# openservo-v28.net
KiCad netlist of a schematic drawn in EAGLE
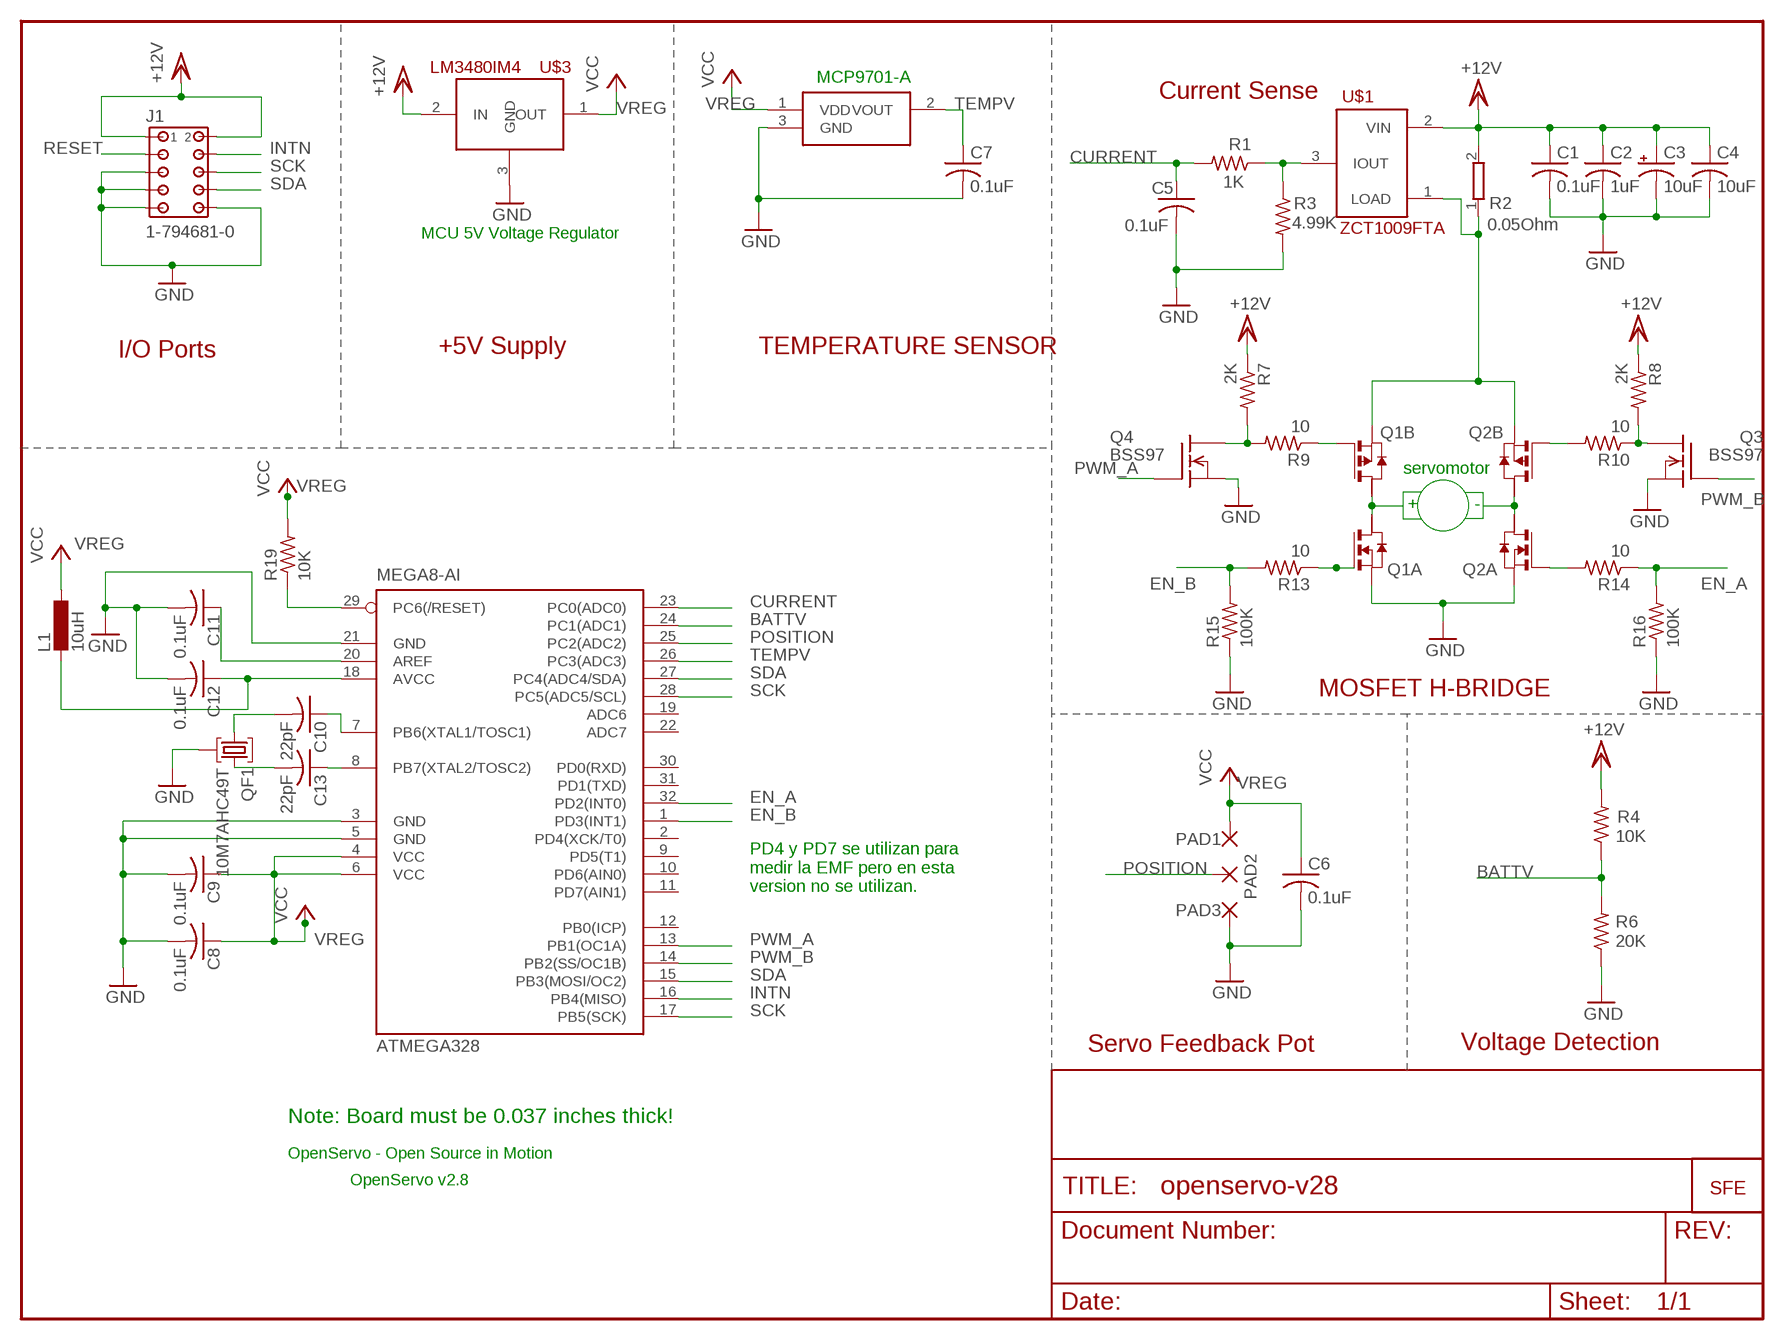
[diagram p0: schematic, sheet 1]

(export (version "E")
  (design (tool "Eeschema 10.0.6"))
  (components
    (comp (ref "ATMEGA328")
      (value "MEGA8-AI")
      (footprint "eagle-import:TQFP32-08")
      (fields (field (name "MPN") "ATMEGA8-16AU"))
      (libsource (lib "eagle-import") (part "MEGA8-AI"))
    )
    (comp (ref "C1")
      (value "0.1uF")
      (footprint "eagle-import:C0402")
      (libsource (lib "eagle-import") (part "C-USC0402"))
    )
    (comp (ref "C2")
      (value "1uF")
      (footprint "eagle-import:C0402")
      (libsource (lib "eagle-import") (part "C-USC0402"))
    )
    (comp (ref "C3")
      (value "10uF")
      (footprint "eagle-import:EIA3528")
      (libsource (lib "eagle-import") (part "CAP_POL3528"))
    )
    (comp (ref "C4")
      (value "10uF")
      (footprint "eagle-import:C0402")
      (libsource (lib "eagle-import") (part "C-USC0402"))
    )
    (comp (ref "C5")
      (value "0.1uF")
      (footprint "eagle-import:C0402")
      (libsource (lib "eagle-import") (part "C-USC0402"))
    )
    (comp (ref "C6")
      (value "0.1uF")
      (footprint "eagle-import:C0402")
      (libsource (lib "eagle-import") (part "C-USC0402"))
    )
    (comp (ref "C7")
      (value "0.1uF")
      (footprint "eagle-import:C0402")
      (libsource (lib "eagle-import") (part "C-USC0402"))
    )
    (comp (ref "C8")
      (value "0.1uF")
      (footprint "eagle-import:C0402")
      (libsource (lib "eagle-import") (part "C-USC0402"))
    )
    (comp (ref "C9")
      (value "0.1uF")
      (footprint "eagle-import:C0402")
      (libsource (lib "eagle-import") (part "C-USC0402"))
    )
    (comp (ref "C10")
      (value "22pF")
      (footprint "eagle-import:C0402")
      (libsource (lib "eagle-import") (part "C-USC0402"))
    )
    (comp (ref "C11")
      (value "0.1uF")
      (footprint "eagle-import:C0402")
      (libsource (lib "eagle-import") (part "C-USC0402"))
    )
    (comp (ref "C12")
      (value "0.1uF")
      (footprint "eagle-import:C0402")
      (libsource (lib "eagle-import") (part "C-USC0402"))
    )
    (comp (ref "C13")
      (value "22pF")
      (footprint "eagle-import:C0402")
      (libsource (lib "eagle-import") (part "C-USC0402"))
    )
    (comp (ref "J1")
      (value "1-794681-0")
      (footprint "eagle-import:1-794681-0")
      (libsource (lib "eagle-import") (part "1-794681-0"))
    )
    (comp (ref "L1")
      (value "10uH")
      (footprint "eagle-import:0204_5")
      (libsource (lib "eagle-import") (part "L-EU0204/5"))
    )
    (comp (ref "PAD1")
      (value "1,6/0,9")
      (footprint "eagle-import:1,6_0,9")
      (libsource (lib "eagle-import") (part "1,6/0,9"))
    )
    (comp (ref "PAD2")
      (value "1,6/0,9")
      (footprint "eagle-import:1,6_0,9")
      (libsource (lib "eagle-import") (part "1,6/0,9"))
    )
    (comp (ref "PAD3")
      (value "1,6/0,9")
      (footprint "eagle-import:1,6_0,9")
      (libsource (lib "eagle-import") (part "1,6/0,9"))
    )
    (comp (ref "Q1")
      (value "PN_MOSFET-SO8")
      (footprint "eagle-import:SO8")
      (libsource (lib "eagle-import") (part "PN_MOSFET-SO8"))
    )
    (comp (ref "Q2")
      (value "PN_MOSFET-SO8")
      (footprint "eagle-import:SO8")
      (libsource (lib "eagle-import") (part "PN_MOSFET-SO8"))
    )
    (comp (ref "Q3")
      (value "BSS97")
      (footprint "eagle-import:TO202")
      (libsource (lib "eagle-import") (part "BSS97"))
    )
    (comp (ref "Q4")
      (value "BSS97")
      (footprint "eagle-import:TO202")
      (libsource (lib "eagle-import") (part "BSS97"))
    )
    (comp (ref "QF1")
      (value "10M7AHC49T")
      (footprint "eagle-import:HC49U")
      (libsource (lib "eagle-import") (part "10MAHC49T7"))
    )
    (comp (ref "R1")
      (value "1K")
      (footprint "eagle-import:R0402")
      (libsource (lib "eagle-import") (part "R-US_R0402"))
    )
    (comp (ref "R2")
      (value "0.05Ohm")
      (footprint "eagle-import:R1206W")
      (libsource (lib "eagle-import") (part "R1206W"))
    )
    (comp (ref "R3")
      (value "4.99K")
      (footprint "eagle-import:R0402")
      (libsource (lib "eagle-import") (part "R-US_R0402"))
    )
    (comp (ref "R4")
      (value "10K")
      (footprint "eagle-import:R0402")
      (libsource (lib "eagle-import") (part "R-US_R0402"))
    )
    (comp (ref "R6")
      (value "20K")
      (footprint "eagle-import:R0402")
      (libsource (lib "eagle-import") (part "R-US_R0402"))
    )
    (comp (ref "R7")
      (value "2K")
      (footprint "eagle-import:R0402")
      (libsource (lib "eagle-import") (part "R-US_R0402"))
    )
    (comp (ref "R8")
      (value "2K")
      (footprint "eagle-import:R0402")
      (libsource (lib "eagle-import") (part "R-US_R0402"))
    )
    (comp (ref "R9")
      (value "10")
      (footprint "eagle-import:R0402")
      (libsource (lib "eagle-import") (part "R-US_R0402"))
    )
    (comp (ref "R10")
      (value "10")
      (footprint "eagle-import:R0402")
      (libsource (lib "eagle-import") (part "R-US_R0402"))
    )
    (comp (ref "R13")
      (value "10")
      (footprint "eagle-import:R0402")
      (libsource (lib "eagle-import") (part "R-US_R0402"))
    )
    (comp (ref "R14")
      (value "10")
      (footprint "eagle-import:R0402")
      (libsource (lib "eagle-import") (part "R-US_R0402"))
    )
    (comp (ref "R15")
      (value "100K")
      (footprint "eagle-import:R0402")
      (libsource (lib "eagle-import") (part "R-US_R0402"))
    )
    (comp (ref "R16")
      (value "100K")
      (footprint "eagle-import:R0402")
      (libsource (lib "eagle-import") (part "R-US_R0402"))
    )
    (comp (ref "R19")
      (value "10K")
      (footprint "eagle-import:R0402")
      (libsource (lib "eagle-import") (part "R-US_R0402"))
    )
    (comp (ref "U$1")
      (value "ZCT1009FTA")
      (footprint "eagle-import:SOT23-3")
      (libsource (lib "eagle-import") (part "ZCT1009FTA"))
    )
    (comp (ref "U$2")
      (value "MCP9701-A")
      (footprint "eagle-import:TO-92")
      (libsource (lib "eagle-import") (part "MCP9701-A"))
    )
    (comp (ref "U$3")
      (value "LM3480IM4")
      (footprint "eagle-import:SOT23-3")
      (libsource (lib "eagle-import") (part "LM3480IM4"))
    )
    (comp (ref "U$7")
      (value "LOGO-SFESK")
      (footprint "eagle-import:SFE-LOGO-FLAME")
      (libsource (lib "eagle-import") (part "LOGO-SFESK"))
    )
  )
  (nets
    (net (code "1") (name "+12V") (class "Default")
      (node (ref "C1") (pin "1") (pinfunction "1_1") (pintype "passive"))
      (node (ref "C2") (pin "1") (pinfunction "1_1") (pintype "passive"))
      (node (ref "C3") (pin "A") (pinfunction "+_A") (pintype "passive"))
      (node (ref "C4") (pin "1") (pinfunction "1_1") (pintype "passive"))
      (node (ref "J1") (pin "1") (pinfunction "1_1") (pintype "passive"))
      (node (ref "J1") (pin "2") (pinfunction "2_2") (pintype "passive"))
      (node (ref "R2") (pin "2") (pinfunction "2_2") (pintype "passive"))
      (node (ref "R4") (pin "2") (pinfunction "2_2") (pintype "passive"))
      (node (ref "R7") (pin "1") (pinfunction "1_1") (pintype "passive"))
      (node (ref "R8") (pin "1") (pinfunction "1_1") (pintype "passive"))
      (node (ref "U$1") (pin "2") (pinfunction "VIN_2") (pintype "bidirectional"))
      (node (ref "U$3") (pin "2") (pinfunction "IN_2") (pintype "bidirectional"))
    )
    (net (code "2") (name "/BATTV") (class "Default")
      (node (ref "ATMEGA328") (pin "24") (pinfunction "PC1(ADC1)_24") (pintype "bidirectional"))
      (node (ref "R4") (pin "1") (pinfunction "1_1") (pintype "passive"))
      (node (ref "R6") (pin "2") (pinfunction "2_2") (pintype "passive"))
    )
    (net (code "3") (name "/CURRENT") (class "Default")
      (node (ref "ATMEGA328") (pin "23") (pinfunction "PC0(ADC0)_23") (pintype "bidirectional"))
      (node (ref "C5") (pin "1") (pinfunction "1_1") (pintype "passive"))
      (node (ref "R1") (pin "2") (pinfunction "2_2") (pintype "passive"))
    )
    (net (code "4") (name "/EN_A") (class "Default")
      (node (ref "ATMEGA328") (pin "32") (pinfunction "PD2(INT0)_32") (pintype "bidirectional"))
      (node (ref "R14") (pin "1") (pinfunction "1_1") (pintype "passive"))
      (node (ref "R16") (pin "2") (pinfunction "2_2") (pintype "passive"))
    )
    (net (code "5") (name "/EN_B") (class "Default")
      (node (ref "ATMEGA328") (pin "1") (pinfunction "PD3(INT1)_1") (pintype "bidirectional"))
      (node (ref "R13") (pin "2") (pinfunction "2_2") (pintype "passive"))
      (node (ref "R15") (pin "2") (pinfunction "2_2") (pintype "passive"))
    )
    (net (code "6") (name "/INTN") (class "Default")
      (node (ref "ATMEGA328") (pin "16") (pinfunction "PB4(MISO)_16") (pintype "bidirectional"))
      (node (ref "J1") (pin "4") (pinfunction "4_4") (pintype "passive"))
    )
    (net (code "7") (name "/POSITION") (class "Default")
      (node (ref "ATMEGA328") (pin "25") (pinfunction "PC2(ADC2)_25") (pintype "bidirectional"))
      (node (ref "PAD2") (pin "1") (pinfunction "P_1") (pintype "passive"))
    )
    (net (code "8") (name "/PWM_A") (class "Default")
      (node (ref "ATMEGA328") (pin "13") (pinfunction "PB1(OC1A)_13") (pintype "bidirectional"))
      (node (ref "Q4") (pin "3") (pinfunction "G_3") (pintype "passive"))
    )
    (net (code "9") (name "/PWM_B") (class "Default")
      (node (ref "ATMEGA328") (pin "14") (pinfunction "PB2(SS/OC1B)_14") (pintype "bidirectional"))
      (node (ref "Q3") (pin "3") (pinfunction "G_3") (pintype "passive"))
    )
    (net (code "10") (name "/RESET") (class "Default")
      (node (ref "ATMEGA328") (pin "29") (pinfunction "PC6(/RESET)_29") (pintype "bidirectional"))
      (node (ref "J1") (pin "3") (pinfunction "3_3") (pintype "passive"))
      (node (ref "R19") (pin "1") (pinfunction "1_1") (pintype "passive"))
    )
    (net (code "11") (name "/SCK") (class "Default")
      (node (ref "ATMEGA328") (pin "17") (pinfunction "PB5(SCK)_17") (pintype "bidirectional"))
      (node (ref "ATMEGA328") (pin "28") (pinfunction "PC5(ADC5/SCL)_28") (pintype "bidirectional"))
      (node (ref "J1") (pin "6") (pinfunction "6_6") (pintype "passive"))
    )
    (net (code "12") (name "/SDA") (class "Default")
      (node (ref "ATMEGA328") (pin "15") (pinfunction "PB3(MOSI/OC2)_15") (pintype "bidirectional"))
      (node (ref "ATMEGA328") (pin "27") (pinfunction "PC4(ADC4/SDA)_27") (pintype "bidirectional"))
      (node (ref "J1") (pin "8") (pinfunction "8_8") (pintype "passive"))
    )
    (net (code "13") (name "/TEMPV") (class "Default")
      (node (ref "ATMEGA328") (pin "26") (pinfunction "PC3(ADC3)_26") (pintype "bidirectional"))
      (node (ref "C7") (pin "1") (pinfunction "1_1") (pintype "passive"))
      (node (ref "U$2") (pin "2") (pinfunction "VOUT_2") (pintype "bidirectional"))
    )
    (net (code "14") (name "GND") (class "Default")
      (node (ref "ATMEGA328") (pin "21") (pinfunction "GND_21") (pintype "power_in"))
      (node (ref "ATMEGA328") (pin "3") (pinfunction "GND_3") (pintype "power_in"))
      (node (ref "ATMEGA328") (pin "5") (pinfunction "GND_5") (pintype "power_in"))
      (node (ref "C1") (pin "2") (pinfunction "2_2") (pintype "passive"))
      (node (ref "C11") (pin "2") (pinfunction "2_2") (pintype "passive"))
      (node (ref "C12") (pin "2") (pinfunction "2_2") (pintype "passive"))
      (node (ref "C2") (pin "2") (pinfunction "2_2") (pintype "passive"))
      (node (ref "C3") (pin "C") (pinfunction "-_C") (pintype "passive"))
      (node (ref "C4") (pin "2") (pinfunction "2_2") (pintype "passive"))
      (node (ref "C5") (pin "2") (pinfunction "2_2") (pintype "passive"))
      (node (ref "C6") (pin "2") (pinfunction "2_2") (pintype "passive"))
      (node (ref "C7") (pin "2") (pinfunction "2_2") (pintype "passive"))
      (node (ref "C8") (pin "2") (pinfunction "2_2") (pintype "passive"))
      (node (ref "C9") (pin "2") (pinfunction "2_2") (pintype "passive"))
      (node (ref "J1") (pin "10") (pinfunction "10_10") (pintype "passive"))
      (node (ref "J1") (pin "5") (pinfunction "5_5") (pintype "passive"))
      (node (ref "J1") (pin "7") (pinfunction "7_7") (pintype "passive"))
      (node (ref "J1") (pin "9") (pinfunction "9_9") (pintype "passive"))
      (node (ref "PAD3") (pin "1") (pinfunction "P_1") (pintype "passive"))
      (node (ref "Q1") (pin "1") (pinfunction "S_1") (pintype "passive"))
      (node (ref "Q2") (pin "1") (pinfunction "S_1") (pintype "passive"))
      (node (ref "Q3") (pin "1") (pinfunction "S_1") (pintype "passive"))
      (node (ref "Q4") (pin "1") (pinfunction "S_1") (pintype "passive"))
      (node (ref "QF1") (pin "2") (pinfunction "2_2") (pintype "passive"))
      (node (ref "R15") (pin "1") (pinfunction "1_1") (pintype "passive"))
      (node (ref "R16") (pin "1") (pinfunction "1_1") (pintype "passive"))
      (node (ref "R3") (pin "2") (pinfunction "2_2") (pintype "passive"))
      (node (ref "R6") (pin "1") (pinfunction "1_1") (pintype "passive"))
      (node (ref "U$2") (pin "3") (pinfunction "GND_3") (pintype "bidirectional"))
      (node (ref "U$3") (pin "3") (pinfunction "GND_3") (pintype "bidirectional"))
    )
    (net (code "15") (name "Net-(ATMEGA328-AREF)") (class "Default")
      (node (ref "ATMEGA328") (pin "20") (pinfunction "AREF_20") (pintype "passive"))
      (node (ref "C11") (pin "1") (pinfunction "1_1") (pintype "passive"))
    )
    (net (code "16") (name "Net-(ATMEGA328-AVCC)") (class "Default")
      (node (ref "ATMEGA328") (pin "18") (pinfunction "AVCC_18") (pintype "power_in"))
      (node (ref "C12") (pin "1") (pinfunction "1_1") (pintype "passive"))
      (node (ref "L1") (pin "2") (pinfunction "2_2") (pintype "passive"))
    )
    (net (code "17") (name "Net-(ATMEGA328-PB6(XTAL1{slash}TOSC1))") (class "Default")
      (node (ref "ATMEGA328") (pin "7") (pinfunction "PB6(XTAL1/TOSC1)_7") (pintype "bidirectional"))
      (node (ref "C10") (pin "1") (pinfunction "1_1") (pintype "passive"))
    )
    (net (code "18") (name "Net-(ATMEGA328-PB7(XTAL2{slash}TOSC2))") (class "Default")
      (node (ref "ATMEGA328") (pin "8") (pinfunction "PB7(XTAL2/TOSC2)_8") (pintype "bidirectional"))
      (node (ref "C13") (pin "1") (pinfunction "1_1") (pintype "passive"))
    )
    (net (code "19") (name "Net-(C10-Pad2)") (class "Default")
      (node (ref "C10") (pin "2") (pinfunction "2_2") (pintype "passive"))
      (node (ref "QF1") (pin "1") (pinfunction "1_1") (pintype "passive"))
    )
    (net (code "20") (name "Net-(C13-Pad2)") (class "Default")
      (node (ref "C13") (pin "2") (pinfunction "2_2") (pintype "passive"))
      (node (ref "QF1") (pin "3") (pinfunction "3_3") (pintype "passive"))
    )
    (net (code "21") (name "Net-(Q1A-D)") (class "Default")
      (node (ref "Q1") (pin "5") (pinfunction "D_5") (pintype "passive"))
      (node (ref "Q1") (pin "7") (pinfunction "D_7") (pintype "passive"))
    )
    (net (code "22") (name "Net-(Q1A-G)") (class "Default")
      (node (ref "Q1") (pin "2") (pinfunction "G_2") (pintype "passive"))
      (node (ref "R13") (pin "1") (pinfunction "1_1") (pintype "passive"))
    )
    (net (code "23") (name "Net-(Q1B-G)") (class "Default")
      (node (ref "Q1") (pin "4") (pinfunction "G_4") (pintype "passive"))
      (node (ref "R9") (pin "1") (pinfunction "1_1") (pintype "passive"))
    )
    (net (code "24") (name "Net-(Q1B-S)") (class "Default")
      (node (ref "Q1") (pin "3") (pinfunction "S_3") (pintype "passive"))
      (node (ref "Q2") (pin "3") (pinfunction "S_3") (pintype "passive"))
      (node (ref "R2") (pin "1") (pinfunction "1_1") (pintype "passive"))
      (node (ref "U$1") (pin "1") (pinfunction "LOAD_1") (pintype "bidirectional"))
    )
    (net (code "25") (name "Net-(Q2A-D)") (class "Default")
      (node (ref "Q2") (pin "5") (pinfunction "D_5") (pintype "passive"))
      (node (ref "Q2") (pin "7") (pinfunction "D_7") (pintype "passive"))
    )
    (net (code "26") (name "Net-(Q2A-G)") (class "Default")
      (node (ref "Q2") (pin "2") (pinfunction "G_2") (pintype "passive"))
      (node (ref "R14") (pin "2") (pinfunction "2_2") (pintype "passive"))
    )
    (net (code "27") (name "Net-(Q2B-G)") (class "Default")
      (node (ref "Q2") (pin "4") (pinfunction "G_4") (pintype "passive"))
      (node (ref "R10") (pin "2") (pinfunction "2_2") (pintype "passive"))
    )
    (net (code "28") (name "Net-(Q3-D)") (class "Default")
      (node (ref "Q3") (pin "2") (pinfunction "D_2") (pintype "passive"))
      (node (ref "R10") (pin "1") (pinfunction "1_1") (pintype "passive"))
      (node (ref "R8") (pin "2") (pinfunction "2_2") (pintype "passive"))
    )
    (net (code "29") (name "Net-(Q4-D)") (class "Default")
      (node (ref "Q4") (pin "2") (pinfunction "D_2") (pintype "passive"))
      (node (ref "R7") (pin "2") (pinfunction "2_2") (pintype "passive"))
      (node (ref "R9") (pin "2") (pinfunction "2_2") (pintype "passive"))
    )
    (net (code "30") (name "Net-(U$1-IOUT)") (class "Default")
      (node (ref "R1") (pin "1") (pinfunction "1_1") (pintype "passive"))
      (node (ref "R3") (pin "1") (pinfunction "1_1") (pintype "passive"))
      (node (ref "U$1") (pin "3") (pinfunction "IOUT_3") (pintype "bidirectional"))
    )
    (net (code "31") (name "VCC") (class "Default")
      (node (ref "ATMEGA328") (pin "4") (pinfunction "VCC_4") (pintype "power_in"))
      (node (ref "ATMEGA328") (pin "6") (pinfunction "VCC_6") (pintype "power_in"))
      (node (ref "C6") (pin "1") (pinfunction "1_1") (pintype "passive"))
      (node (ref "C8") (pin "1") (pinfunction "1_1") (pintype "passive"))
      (node (ref "C9") (pin "1") (pinfunction "1_1") (pintype "passive"))
      (node (ref "L1") (pin "1") (pinfunction "1_1") (pintype "passive"))
      (node (ref "PAD1") (pin "1") (pinfunction "P_1") (pintype "passive"))
      (node (ref "R19") (pin "2") (pinfunction "2_2") (pintype "passive"))
      (node (ref "U$2") (pin "1") (pinfunction "VDD_1") (pintype "bidirectional"))
      (node (ref "U$3") (pin "1") (pinfunction "OUT_1") (pintype "bidirectional"))
    )
    (net (code "32") (name "unconnected-(ATMEGA328-ADC6-Pad19)") (class "Default")
      (node (ref "ATMEGA328") (pin "19") (pinfunction "ADC6_19") (pintype "bidirectional"))
    )
    (net (code "33") (name "unconnected-(ATMEGA328-ADC7-Pad22)") (class "Default")
      (node (ref "ATMEGA328") (pin "22") (pinfunction "ADC7_22") (pintype "bidirectional"))
    )
    (net (code "34") (name "unconnected-(ATMEGA328-PB0(ICP)-Pad12)") (class "Default")
      (node (ref "ATMEGA328") (pin "12") (pinfunction "PB0(ICP)_12") (pintype "bidirectional"))
    )
    (net (code "35") (name "unconnected-(ATMEGA328-PD0(RXD)-Pad30)") (class "Default")
      (node (ref "ATMEGA328") (pin "30") (pinfunction "PD0(RXD)_30") (pintype "bidirectional"))
    )
    (net (code "36") (name "unconnected-(ATMEGA328-PD1(TXD)-Pad31)") (class "Default")
      (node (ref "ATMEGA328") (pin "31") (pinfunction "PD1(TXD)_31") (pintype "bidirectional"))
    )
    (net (code "37") (name "unconnected-(ATMEGA328-PD4(XCK{slash}T0)-Pad2)") (class "Default")
      (node (ref "ATMEGA328") (pin "2") (pinfunction "PD4(XCK/T0)_2") (pintype "bidirectional"))
    )
    (net (code "38") (name "unconnected-(ATMEGA328-PD5(T1)-Pad9)") (class "Default")
      (node (ref "ATMEGA328") (pin "9") (pinfunction "PD5(T1)_9") (pintype "bidirectional"))
    )
    (net (code "39") (name "unconnected-(ATMEGA328-PD6(AIN0)-Pad10)") (class "Default")
      (node (ref "ATMEGA328") (pin "10") (pinfunction "PD6(AIN0)_10") (pintype "bidirectional"))
    )
    (net (code "40") (name "unconnected-(ATMEGA328-PD7(AIN1)-Pad11)") (class "Default")
      (node (ref "ATMEGA328") (pin "11") (pinfunction "PD7(AIN1)_11") (pintype "bidirectional"))
    )
    (net (code "41") (name "unconnected-(Q1A-D2-Pad8)") (class "Default")
      (node (ref "Q1") (pin "8") (pinfunction "D2_8") (pintype "passive"))
    )
    (net (code "42") (name "unconnected-(Q1B-D2-Pad6)") (class "Default")
      (node (ref "Q1") (pin "6") (pinfunction "D2_6") (pintype "passive"))
    )
    (net (code "43") (name "unconnected-(Q2A-D2-Pad8)") (class "Default")
      (node (ref "Q2") (pin "8") (pinfunction "D2_8") (pintype "passive"))
    )
    (net (code "44") (name "unconnected-(Q2B-D2-Pad6)") (class "Default")
      (node (ref "Q2") (pin "6") (pinfunction "D2_6") (pintype "passive"))
    )
  )
)
